# eps_imu.net
KiCad netlist of a schematic drawn in Altium Designer
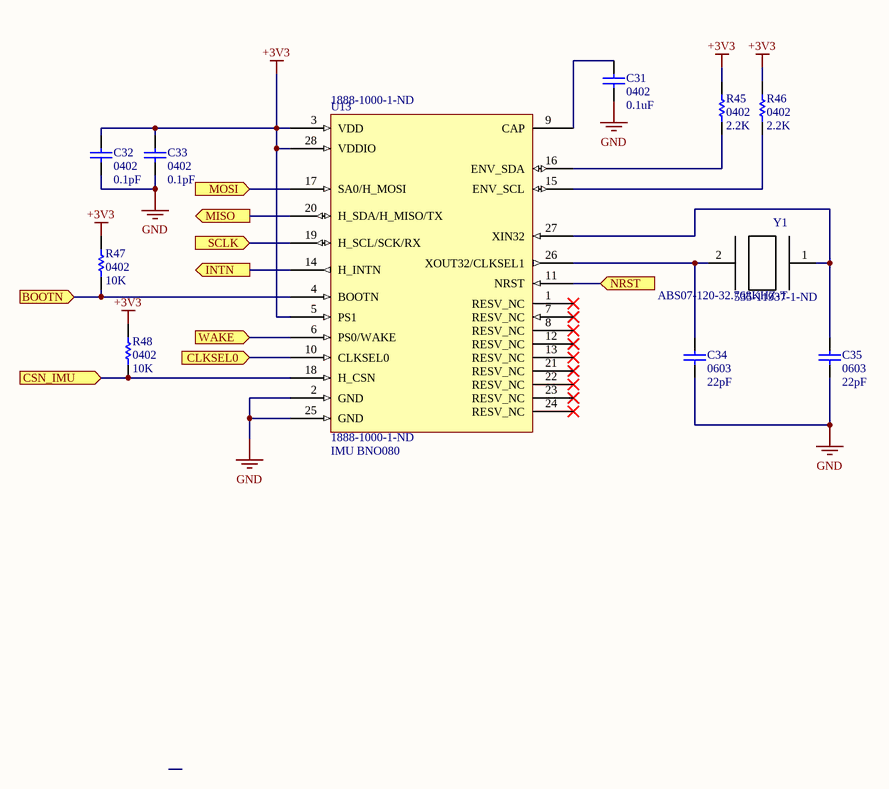
[diagram p0: eps_imu.SchDoc]

(export (version "E")
  (design (tool "Eeschema 10.0.6"))
  (components
    (comp (ref "C31")
      (value "0402")
      (footprint "CAP0402R")
      (description "0402 capacitor")
      (fields (field (name "ALTIUM_VALUE") "0.1uF"))
      (libsource (lib "heron-general") (part "CAP0402"))
    )
    (comp (ref "C32")
      (value "0402")
      (footprint "CAP0402R")
      (description "0402 capacitor")
      (fields (field (name "ALTIUM_VALUE") "0.1pF"))
      (libsource (lib "heron-general") (part "CAP0402"))
    )
    (comp (ref "C33")
      (value "0402")
      (footprint "CAP0402R")
      (description "0402 capacitor")
      (fields (field (name "ALTIUM_VALUE") "0.1pF"))
      (libsource (lib "heron-general") (part "CAP0402"))
    )
    (comp (ref "C34")
      (value "0603")
      (footprint "CAP0603R")
      (description "0603 capacitor")
      (fields (field (name "ALTIUM_VALUE") "22pF"))
      (libsource (lib "heron-general") (part "CAP0603"))
    )
    (comp (ref "C35")
      (value "0603")
      (footprint "CAP0603R")
      (description "0603 capacitor")
      (fields (field (name "ALTIUM_VALUE") "22pF"))
      (libsource (lib "heron-general") (part "CAP0603"))
    )
    (comp (ref "R45")
      (value "0402")
      (footprint "RES0402R")
      (description "0402 resistor")
      (fields (field (name "ALTIUM_VALUE") "2.2K"))
      (libsource (lib "heron-general") (part "RES0402"))
    )
    (comp (ref "R46")
      (value "0402")
      (footprint "RES0402R")
      (description "0402 resistor")
      (fields (field (name "ALTIUM_VALUE") "2.2K"))
      (libsource (lib "heron-general") (part "RES0402"))
    )
    (comp (ref "R47")
      (value "0402")
      (footprint "RES0402R")
      (description "0402 resistor")
      (fields (field (name "ALTIUM_VALUE") "10K"))
      (libsource (lib "heron-general") (part "RES0402"))
    )
    (comp (ref "R48")
      (value "0402")
      (footprint "RES0402R")
      (description "0402 resistor")
      (fields (field (name "ALTIUM_VALUE") "10K"))
      (libsource (lib "heron-general") (part "RES0402"))
    )
    (comp (ref "U13")
      (value "IMU BNO080")
      (footprint "1888-1000-1-ND")
      (description "ACCEL/GYRO/MAG I2C 32BIT")
      (fields
        (field (name "MANUFACTURER") "Hillcrest Laboratories")
        (field (name "MANUFACTURER PART NUMBER") "BNO080")
        (field (name "SUPPLIER PART NUMBER 1") "1888-1000-1-ND")
      )
      (libsource (lib "heron-general") (part "IMU BNO080"))
    )
    (comp (ref "Y1")
      (value "ABS07-120-32.768KHZ-T")
      (footprint "ABS07-120-32.768")
      (fields
        (field (name "MF") "Abracon")
        (field (name "TOLERANCE") "20ppm")
        (field (name "SUPPLIER PART NUMBER 1") "535-11937-1-ND")
      )
      (libsource (lib "ABS07-120-32.768KHZ-T") (part "ABS07-120-32.768KHZ-T"))
    )
  )
  (nets
    (net (code "1") (name "+3V3") (class "Default")
      (node (ref "C32") (pin "2") (pinfunction "2_2") (pintype "passive"))
      (node (ref "C33") (pin "2") (pinfunction "2_2") (pintype "passive"))
      (node (ref "R45") (pin "2") (pinfunction "2_2") (pintype "passive"))
      (node (ref "R46") (pin "2") (pinfunction "2_2") (pintype "passive"))
      (node (ref "R47") (pin "2") (pinfunction "2_2") (pintype "passive"))
      (node (ref "R48") (pin "2") (pinfunction "2_2") (pintype "passive"))
      (node (ref "U13") (pin "28") (pinfunction "VDDIO_28") (pintype "input"))
      (node (ref "U13") (pin "3") (pinfunction "VDD_3") (pintype "input"))
      (node (ref "U13") (pin "5") (pinfunction "PS1_5") (pintype "input"))
    )
    (net (code "2") (name "/BOOTN") (class "Default")
      (node (ref "R47") (pin "1") (pinfunction "1_1") (pintype "passive"))
      (node (ref "U13") (pin "4") (pinfunction "BOOTN_4") (pintype "input"))
    )
    (net (code "3") (name "/CLKSEL0") (class "Default")
      (node (ref "U13") (pin "10") (pinfunction "CLKSEL0_10") (pintype "input"))
    )
    (net (code "4") (name "/CSN_IMU") (class "Default")
      (node (ref "R48") (pin "1") (pinfunction "1_1") (pintype "passive"))
      (node (ref "U13") (pin "18") (pinfunction "H_CSN_18") (pintype "input"))
    )
    (net (code "5") (name "/INTN") (class "Default")
      (node (ref "U13") (pin "14") (pinfunction "H_INTN_14") (pintype "output"))
    )
    (net (code "6") (name "/MISO") (class "Default")
      (node (ref "U13") (pin "20") (pinfunction "H_SDA/H_MISO/TX_20") (pintype "bidirectional"))
    )
    (net (code "7") (name "/MOSI") (class "Default")
      (node (ref "U13") (pin "17") (pinfunction "SA0/H_MOSI_17") (pintype "input"))
    )
    (net (code "8") (name "/NRST") (class "Default")
      (node (ref "U13") (pin "11") (pinfunction "NRST_11") (pintype "input"))
    )
    (net (code "9") (name "/SCLK") (class "Default")
      (node (ref "U13") (pin "19") (pinfunction "H_SCL/SCK/RX_19") (pintype "bidirectional"))
    )
    (net (code "10") (name "/WAKE") (class "Default")
      (node (ref "U13") (pin "6") (pinfunction "PS0/WAKE_6") (pintype "input"))
    )
    (net (code "11") (name "GND") (class "Default")
      (node (ref "C31") (pin "1") (pinfunction "1_1") (pintype "passive"))
      (node (ref "C32") (pin "1") (pinfunction "1_1") (pintype "passive"))
      (node (ref "C33") (pin "1") (pinfunction "1_1") (pintype "passive"))
      (node (ref "C34") (pin "1") (pinfunction "1_1") (pintype "passive"))
      (node (ref "C35") (pin "1") (pinfunction "1_1") (pintype "passive"))
      (node (ref "U13") (pin "2") (pinfunction "GND_2") (pintype "input"))
      (node (ref "U13") (pin "25") (pinfunction "GND_25") (pintype "input"))
    )
    (net (code "12") (name "Net-(U13-CAP)") (class "Default")
      (node (ref "C31") (pin "2") (pinfunction "2_2") (pintype "passive"))
      (node (ref "U13") (pin "9") (pinfunction "CAP_9") (pintype "passive"))
    )
    (net (code "13") (name "Net-(U13-ENV_SCL)") (class "Default")
      (node (ref "R46") (pin "1") (pinfunction "1_1") (pintype "passive"))
      (node (ref "U13") (pin "15") (pinfunction "ENV_SCL_15") (pintype "bidirectional"))
    )
    (net (code "14") (name "Net-(U13-ENV_SDA)") (class "Default")
      (node (ref "R45") (pin "1") (pinfunction "1_1") (pintype "passive"))
      (node (ref "U13") (pin "16") (pinfunction "ENV_SDA_16") (pintype "bidirectional"))
    )
    (net (code "15") (name "Net-(U13-XIN32)") (class "Default")
      (node (ref "C35") (pin "2") (pinfunction "2_2") (pintype "passive"))
      (node (ref "U13") (pin "27") (pinfunction "XIN32_27") (pintype "input"))
      (node (ref "Y1") (pin "1") (pinfunction "1_1") (pintype "passive"))
    )
    (net (code "16") (name "Net-(U13-XOUT32{slash}CLKSEL1)") (class "Default")
      (node (ref "C34") (pin "2") (pinfunction "2_2") (pintype "passive"))
      (node (ref "U13") (pin "26") (pinfunction "XOUT32/CLKSEL1_26") (pintype "output"))
      (node (ref "Y1") (pin "2") (pinfunction "2_2") (pintype "passive"))
    )
    (net (code "17") (name "unconnected-(U13-RESV_NC-Pad1)") (class "Default")
      (node (ref "U13") (pin "1") (pinfunction "RESV_NC_1") (pintype "passive+no_connect"))
    )
    (net (code "18") (name "unconnected-(U13-RESV_NC-Pad7)") (class "Default")
      (node (ref "U13") (pin "7") (pinfunction "RESV_NC_7") (pintype "input+no_connect"))
    )
    (net (code "19") (name "unconnected-(U13-RESV_NC-Pad8)") (class "Default")
      (node (ref "U13") (pin "8") (pinfunction "RESV_NC_8") (pintype "passive+no_connect"))
    )
    (net (code "20") (name "unconnected-(U13-RESV_NC-Pad12)") (class "Default")
      (node (ref "U13") (pin "12") (pinfunction "RESV_NC_12") (pintype "passive+no_connect"))
    )
    (net (code "21") (name "unconnected-(U13-RESV_NC-Pad13)") (class "Default")
      (node (ref "U13") (pin "13") (pinfunction "RESV_NC_13") (pintype "passive+no_connect"))
    )
    (net (code "22") (name "unconnected-(U13-RESV_NC-Pad21)") (class "Default")
      (node (ref "U13") (pin "21") (pinfunction "RESV_NC_21") (pintype "passive+no_connect"))
    )
    (net (code "23") (name "unconnected-(U13-RESV_NC-Pad22)") (class "Default")
      (node (ref "U13") (pin "22") (pinfunction "RESV_NC_22") (pintype "passive+no_connect"))
    )
    (net (code "24") (name "unconnected-(U13-RESV_NC-Pad23)") (class "Default")
      (node (ref "U13") (pin "23") (pinfunction "RESV_NC_23") (pintype "passive+no_connect"))
    )
    (net (code "25") (name "unconnected-(U13-RESV_NC-Pad24)") (class "Default")
      (node (ref "U13") (pin "24") (pinfunction "RESV_NC_24") (pintype "passive+no_connect"))
    )
  )
)
